# Sensor.net
KiCad netlist of a schematic drawn in Altium Designer
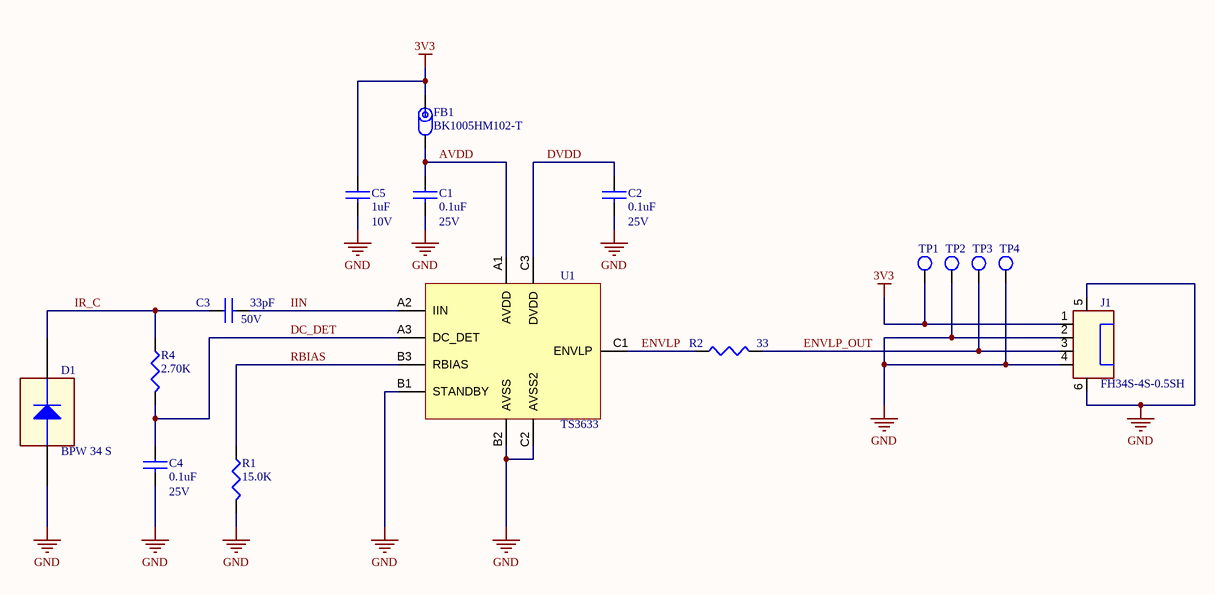
[diagram p0: Sensor.SchDoc]

(export (version "E")
  (design (tool "Eeschema 10.0.6"))
  (components
    (comp (ref "C1")
      (value "0.1uF")
      (footprint "0402-IPCsm_55")
      (description "CAP CER .10UF 25V X5R 0402")
      (fields
        (field (name "VOLTAGE") "25V")
        (field (name "MFG") "Taiyo Yuden")
        (field (name "TOLERANCE") "10%")
      )
      (libsource (lib "SynapseLibrary") (part "CAP"))
    )
    (comp (ref "C2")
      (value "0.1uF")
      (footprint "0402-IPCsm_55")
      (description "CAP CER .10UF 25V X5R 0402")
      (fields
        (field (name "VOLTAGE") "25V")
        (field (name "MFG") "Taiyo Yuden")
        (field (name "TOLERANCE") "10%")
      )
      (libsource (lib "SynapseLibrary") (part "CAP"))
    )
    (comp (ref "C3")
      (value "33pF")
      (footprint "0201-IPCsm_33")
      (description "CAP CER 33PF 50V 5% C0G 0201")
      (fields
        (field (name "VOLTAGE") "50V")
        (field (name "MFG") "TDK Corporation")
        (field (name "TOLERANCE") "5%")
      )
      (libsource (lib "SynapseLibrary") (part "CAP"))
    )
    (comp (ref "C4")
      (value "0.1uF")
      (footprint "0402-IPCsm_55")
      (description "CAP CER .10UF 25V X5R 0402")
      (fields
        (field (name "VOLTAGE") "25V")
        (field (name "MFG") "Taiyo Yuden")
        (field (name "TOLERANCE") "10%")
      )
      (libsource (lib "SynapseLibrary") (part "CAP"))
    )
    (comp (ref "C5")
      (value "1uF")
      (footprint "0402-IPCsm_55")
      (description "CAP CER 1UF 10V 10% X5R 0402")
      (fields (field (name "VOLTAGE") "10V") (field (name "MFG") "MURATA") (field (name "TOLERANCE") "10%"))
      (libsource (lib "SynapseLibrary") (part "CAP"))
    )
    (comp (ref "D1")
      (value "BPW 34 S")
      (footprint "PHOTODIODE_OSRAM_BPW34S")
      (description "PHOTODIODE PIN HI SPEED HI SENS")
      (fields (field (name "MFG") "OSRAM") (field (name "VOLTAGE") "32V"))
      (libsource (lib "SynapseLibrary") (part "BPW_34_S"))
    )
    (comp (ref "FB1")
      (value "BK1005HM102-T")
      (footprint "ind-0402_55")
      (description "FERRITE BEAD 1000 OHM 0402")
      (fields (field (name "MFG") "Taiyo Yuden"))
      (libsource (lib "SynapseLibrary") (part "BK0603HM471-T"))
    )
    (comp (ref "J1")
      (value "FH34S-4S-0.5SH")
      (footprint "con_hirose_FH34SRJ-4S")
      (description "CONN FFC FPC 4POS 0.50MM R/A")
      (fields (field (name "MFG") "HIROSE"))
      (libsource (lib "SynapseLibrary") (part "HEADER 4 TABS"))
    )
    (comp (ref "R1")
      (value "15.0K")
      (footprint "0201-IPCsm_26")
      (description "RES 15.0K OHM 1/20W 1% 0201 SMD")
      (fields (field (name "TOLERANCE") "1.00%") (field (name "MFG") "Panasonic"))
      (libsource (lib "SynapseLibrary") (part "RES"))
    )
    (comp (ref "R2")
      (value "33")
      (footprint "0201-IPCsm_26")
      (description "RES 33 OHM 1/20W 1% 0201 SMD")
      (fields (field (name "TOLERANCE") "1.00%") (field (name "VOLTAGE") "50V"))
      (libsource (lib "SynapseLibrary") (part "RES"))
    )
    (comp (ref "R4")
      (value "2.70K")
      (footprint "0201-IPCsm_26")
      (description "RES 2.70K OHM 1/20W 1% 0201 SMD")
      (fields (field (name "TOLERANCE") "1.00%") (field (name "MFG") "PANASONIC"))
      (libsource (lib "SynapseLibrary") (part "RES"))
    )
    (comp (ref "TP1")
      (value "tp-1mm")
      (footprint "TP-S100_SMT")
      (description "TESTPOINT, 1MM SMD, Square pad, Round SM opening")
      (fields (field (name "MFG") "NA"))
      (libsource (lib "SynapseLibrary") (part "tp_smt"))
    )
    (comp (ref "TP2")
      (value "tp-1mm")
      (footprint "TP-S100_SMT")
      (description "TESTPOINT, 1MM SMD, Square pad, Round SM opening")
      (fields (field (name "MFG") "NA"))
      (libsource (lib "SynapseLibrary") (part "tp_smt"))
    )
    (comp (ref "TP3")
      (value "tp-1mm")
      (footprint "TP-S100_SMT")
      (description "TESTPOINT, 1MM SMD, Square pad, Round SM opening")
      (fields (field (name "MFG") "NA"))
      (libsource (lib "SynapseLibrary") (part "tp_smt"))
    )
    (comp (ref "TP4")
      (value "tp-1mm")
      (footprint "TP-S100_SMT")
      (description "TESTPOINT, 1MM SMD, Square pad, Round SM opening")
      (fields (field (name "MFG") "NA"))
      (libsource (lib "SynapseLibrary") (part "tp_smt"))
    )
    (comp (ref "U1")
      (value "TS3633")
      (footprint "BGA9_166X166X61_50p")
      (description "Optical Receiver for VR Gaming System")
      (fields (field (name "MFG") "Triad Semiconductor"))
      (libsource (lib "SynapseLibrary") (part "TS3633"))
    )
  )
  (nets
    (net (code "1") (name "/AVDD") (class "Default")
      (node (ref "C1") (pin "1") (pinfunction "1_1") (pintype "passive"))
      (node (ref "FB1") (pin "2") (pinfunction "2_2") (pintype "passive"))
      (node (ref "U1") (pin "A1") (pinfunction "AVDD_A1") (pintype "passive"))
    )
    (net (code "2") (name "/DC_DET") (class "Default")
      (node (ref "C4") (pin "1") (pinfunction "1_1") (pintype "passive"))
      (node (ref "R4") (pin "2") (pinfunction "2_2") (pintype "passive"))
      (node (ref "U1") (pin "A3") (pinfunction "DC_DET_A3") (pintype "passive"))
    )
    (net (code "3") (name "/DVDD") (class "Default")
      (node (ref "C2") (pin "1") (pinfunction "1_1") (pintype "passive"))
      (node (ref "U1") (pin "C3") (pinfunction "DVDD_C3") (pintype "passive"))
    )
    (net (code "4") (name "/ENVLP") (class "Default")
      (node (ref "R2") (pin "1") (pinfunction "1_1") (pintype "passive"))
      (node (ref "U1") (pin "C1") (pinfunction "ENVLP_C1") (pintype "passive"))
    )
    (net (code "5") (name "/ENVLP_OUT") (class "Default")
      (node (ref "J1") (pin "3") (pinfunction "3_3") (pintype "passive"))
      (node (ref "R2") (pin "2") (pinfunction "2_2") (pintype "passive"))
      (node (ref "TP3") (pin "1") (pinfunction "TP_1") (pintype "passive"))
    )
    (net (code "6") (name "/IIN") (class "Default")
      (node (ref "C3") (pin "2") (pinfunction "2_2") (pintype "passive"))
      (node (ref "U1") (pin "A2") (pinfunction "IIN_A2") (pintype "passive"))
    )
    (net (code "7") (name "/IR_C") (class "Default")
      (node (ref "C3") (pin "1") (pinfunction "1_1") (pintype "passive"))
      (node (ref "D1") (pin "2") (pinfunction "2_2") (pintype "passive"))
      (node (ref "R4") (pin "1") (pinfunction "1_1") (pintype "passive"))
    )
    (net (code "8") (name "/RBIAS") (class "Default")
      (node (ref "R1") (pin "1") (pinfunction "1_1") (pintype "passive"))
      (node (ref "U1") (pin "B3") (pinfunction "RBIAS_B3") (pintype "passive"))
    )
    (net (code "9") (name "3V3") (class "Default")
      (node (ref "C5") (pin "1") (pinfunction "1_1") (pintype "passive"))
      (node (ref "FB1") (pin "1") (pinfunction "1_1") (pintype "passive"))
      (node (ref "J1") (pin "1") (pinfunction "1_1") (pintype "passive"))
      (node (ref "TP1") (pin "1") (pinfunction "TP_1") (pintype "passive"))
    )
    (net (code "10") (name "GND") (class "Default")
      (node (ref "C1") (pin "2") (pinfunction "2_2") (pintype "passive"))
      (node (ref "C2") (pin "2") (pinfunction "2_2") (pintype "passive"))
      (node (ref "C4") (pin "2") (pinfunction "2_2") (pintype "passive"))
      (node (ref "C5") (pin "2") (pinfunction "2_2") (pintype "passive"))
      (node (ref "D1") (pin "1") (pinfunction "1_1") (pintype "passive"))
      (node (ref "J1") (pin "2") (pinfunction "2_2") (pintype "passive"))
      (node (ref "J1") (pin "4") (pinfunction "4_4") (pintype "passive"))
      (node (ref "J1") (pin "5") (pinfunction "TAB1_5") (pintype "passive"))
      (node (ref "J1") (pin "6") (pinfunction "TAB2_6") (pintype "passive"))
      (node (ref "R1") (pin "2") (pinfunction "2_2") (pintype "passive"))
      (node (ref "TP2") (pin "1") (pinfunction "TP_1") (pintype "passive"))
      (node (ref "TP4") (pin "1") (pinfunction "TP_1") (pintype "passive"))
      (node (ref "U1") (pin "B1") (pinfunction "STANDBY_B1") (pintype "passive"))
      (node (ref "U1") (pin "B2") (pinfunction "AVSS_B2") (pintype "passive"))
      (node (ref "U1") (pin "C2") (pinfunction "AVSS2_C2") (pintype "passive"))
    )
  )
)
